# SC60224.net
KiCad netlist of a schematic drawn in Altium Designer
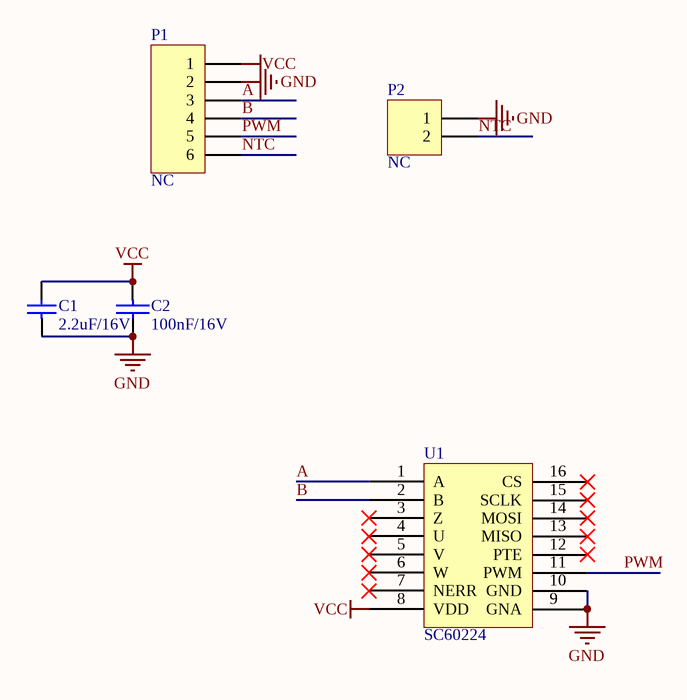
[diagram p0: SC60224.SchDoc]

(export (version "E")
  (design (tool "Eeschema 10.0.6"))
  (components
    (comp (ref "C1") (value "2.2uF/16V") (footprint "C0603") (libsource (lib "zijianku") (part "cap")))
    (comp (ref "C2")
      (value "100nF/16V")
      (footprint "C0402")
      (description "Capacitor")
      (libsource (lib "*") (part "CAP"))
    )
    (comp (ref "P1")
      (value "NC")
      (footprint "HDR1X6")
      (description "Header, 6-Pin")
      (fields (field (name "PUBLISHER") "Altium Limited"))
      (libsource (lib "Common Headers") (part "Header 6"))
    )
    (comp (ref "P2")
      (value "NC")
      (footprint "HDR1X2")
      (description "Header, 2-Pin")
      (fields (field (name "PUBLISHER") "Altium Limited"))
      (libsource (lib "Common Headers") (part "Header 2"))
    )
    (comp (ref "U1") (value "SC60224") (footprint "SSOP-16") (libsource (lib "zijianku") (part "SC60224")))
  )
  (nets
    (net (code "1") (name "/A") (class "Default")
      (node (ref "P1") (pin "3") (pinfunction "3_3") (pintype "passive"))
      (node (ref "U1") (pin "1") (pinfunction "A_1") (pintype "passive"))
    )
    (net (code "2") (name "/B") (class "Default")
      (node (ref "P1") (pin "4") (pinfunction "4_4") (pintype "passive"))
      (node (ref "U1") (pin "2") (pinfunction "B_2") (pintype "passive"))
    )
    (net (code "3") (name "/NTC") (class "Default")
      (node (ref "P1") (pin "6") (pinfunction "6_6") (pintype "passive"))
      (node (ref "P2") (pin "2") (pinfunction "2_2") (pintype "passive"))
    )
    (net (code "4") (name "/PWM") (class "Default")
      (node (ref "P1") (pin "5") (pinfunction "5_5") (pintype "passive"))
      (node (ref "U1") (pin "11") (pinfunction "PWM_11") (pintype "passive"))
    )
    (net (code "5") (name "GND") (class "Default")
      (node (ref "C1") (pin "1") (pinfunction "0_1") (pintype "passive"))
      (node (ref "C2") (pin "2") (pinfunction "2_2") (pintype "passive"))
      (node (ref "P1") (pin "2") (pinfunction "2_2") (pintype "passive"))
      (node (ref "P2") (pin "1") (pinfunction "1_1") (pintype "passive"))
      (node (ref "U1") (pin "10") (pinfunction "GND_10") (pintype "passive"))
      (node (ref "U1") (pin "9") (pinfunction "GNA_9") (pintype "passive"))
    )
    (net (code "6") (name "VCC") (class "Default")
      (node (ref "C1") (pin "2") (pinfunction "1_2") (pintype "passive"))
      (node (ref "C2") (pin "1") (pinfunction "1_1") (pintype "passive"))
      (node (ref "P1") (pin "1") (pinfunction "1_1") (pintype "passive"))
      (node (ref "U1") (pin "8") (pinfunction "VDD_8") (pintype "passive"))
    )
    (net (code "7") (name "unconnected-(U1-CS-Pad16)") (class "Default")
      (node (ref "U1") (pin "16") (pinfunction "CS_16") (pintype "passive+no_connect"))
    )
    (net (code "8") (name "unconnected-(U1-MISO-Pad13)") (class "Default")
      (node (ref "U1") (pin "13") (pinfunction "MISO_13") (pintype "passive+no_connect"))
    )
    (net (code "9") (name "unconnected-(U1-MOSI-Pad14)") (class "Default")
      (node (ref "U1") (pin "14") (pinfunction "MOSI_14") (pintype "passive+no_connect"))
    )
    (net (code "10") (name "unconnected-(U1-NERR-Pad7)") (class "Default")
      (node (ref "U1") (pin "7") (pinfunction "NERR_7") (pintype "passive+no_connect"))
    )
    (net (code "11") (name "unconnected-(U1-PTE-Pad12)") (class "Default")
      (node (ref "U1") (pin "12") (pinfunction "PTE_12") (pintype "passive+no_connect"))
    )
    (net (code "12") (name "unconnected-(U1-SCLK-Pad15)") (class "Default")
      (node (ref "U1") (pin "15") (pinfunction "SCLK_15") (pintype "passive+no_connect"))
    )
    (net (code "13") (name "unconnected-(U1-U-Pad4)") (class "Default")
      (node (ref "U1") (pin "4") (pinfunction "U_4") (pintype "passive+no_connect"))
    )
    (net (code "14") (name "unconnected-(U1-V-Pad5)") (class "Default")
      (node (ref "U1") (pin "5") (pinfunction "V_5") (pintype "passive+no_connect"))
    )
    (net (code "15") (name "unconnected-(U1-W-Pad6)") (class "Default")
      (node (ref "U1") (pin "6") (pinfunction "W_6") (pintype "passive+no_connect"))
    )
    (net (code "16") (name "unconnected-(U1-Z-Pad3)") (class "Default")
      (node (ref "U1") (pin "3") (pinfunction "Z_3") (pintype "passive+no_connect"))
    )
  )
)
